# GL3520_4_Ports.net
KiCad netlist of a schematic drawn in Altium Designer
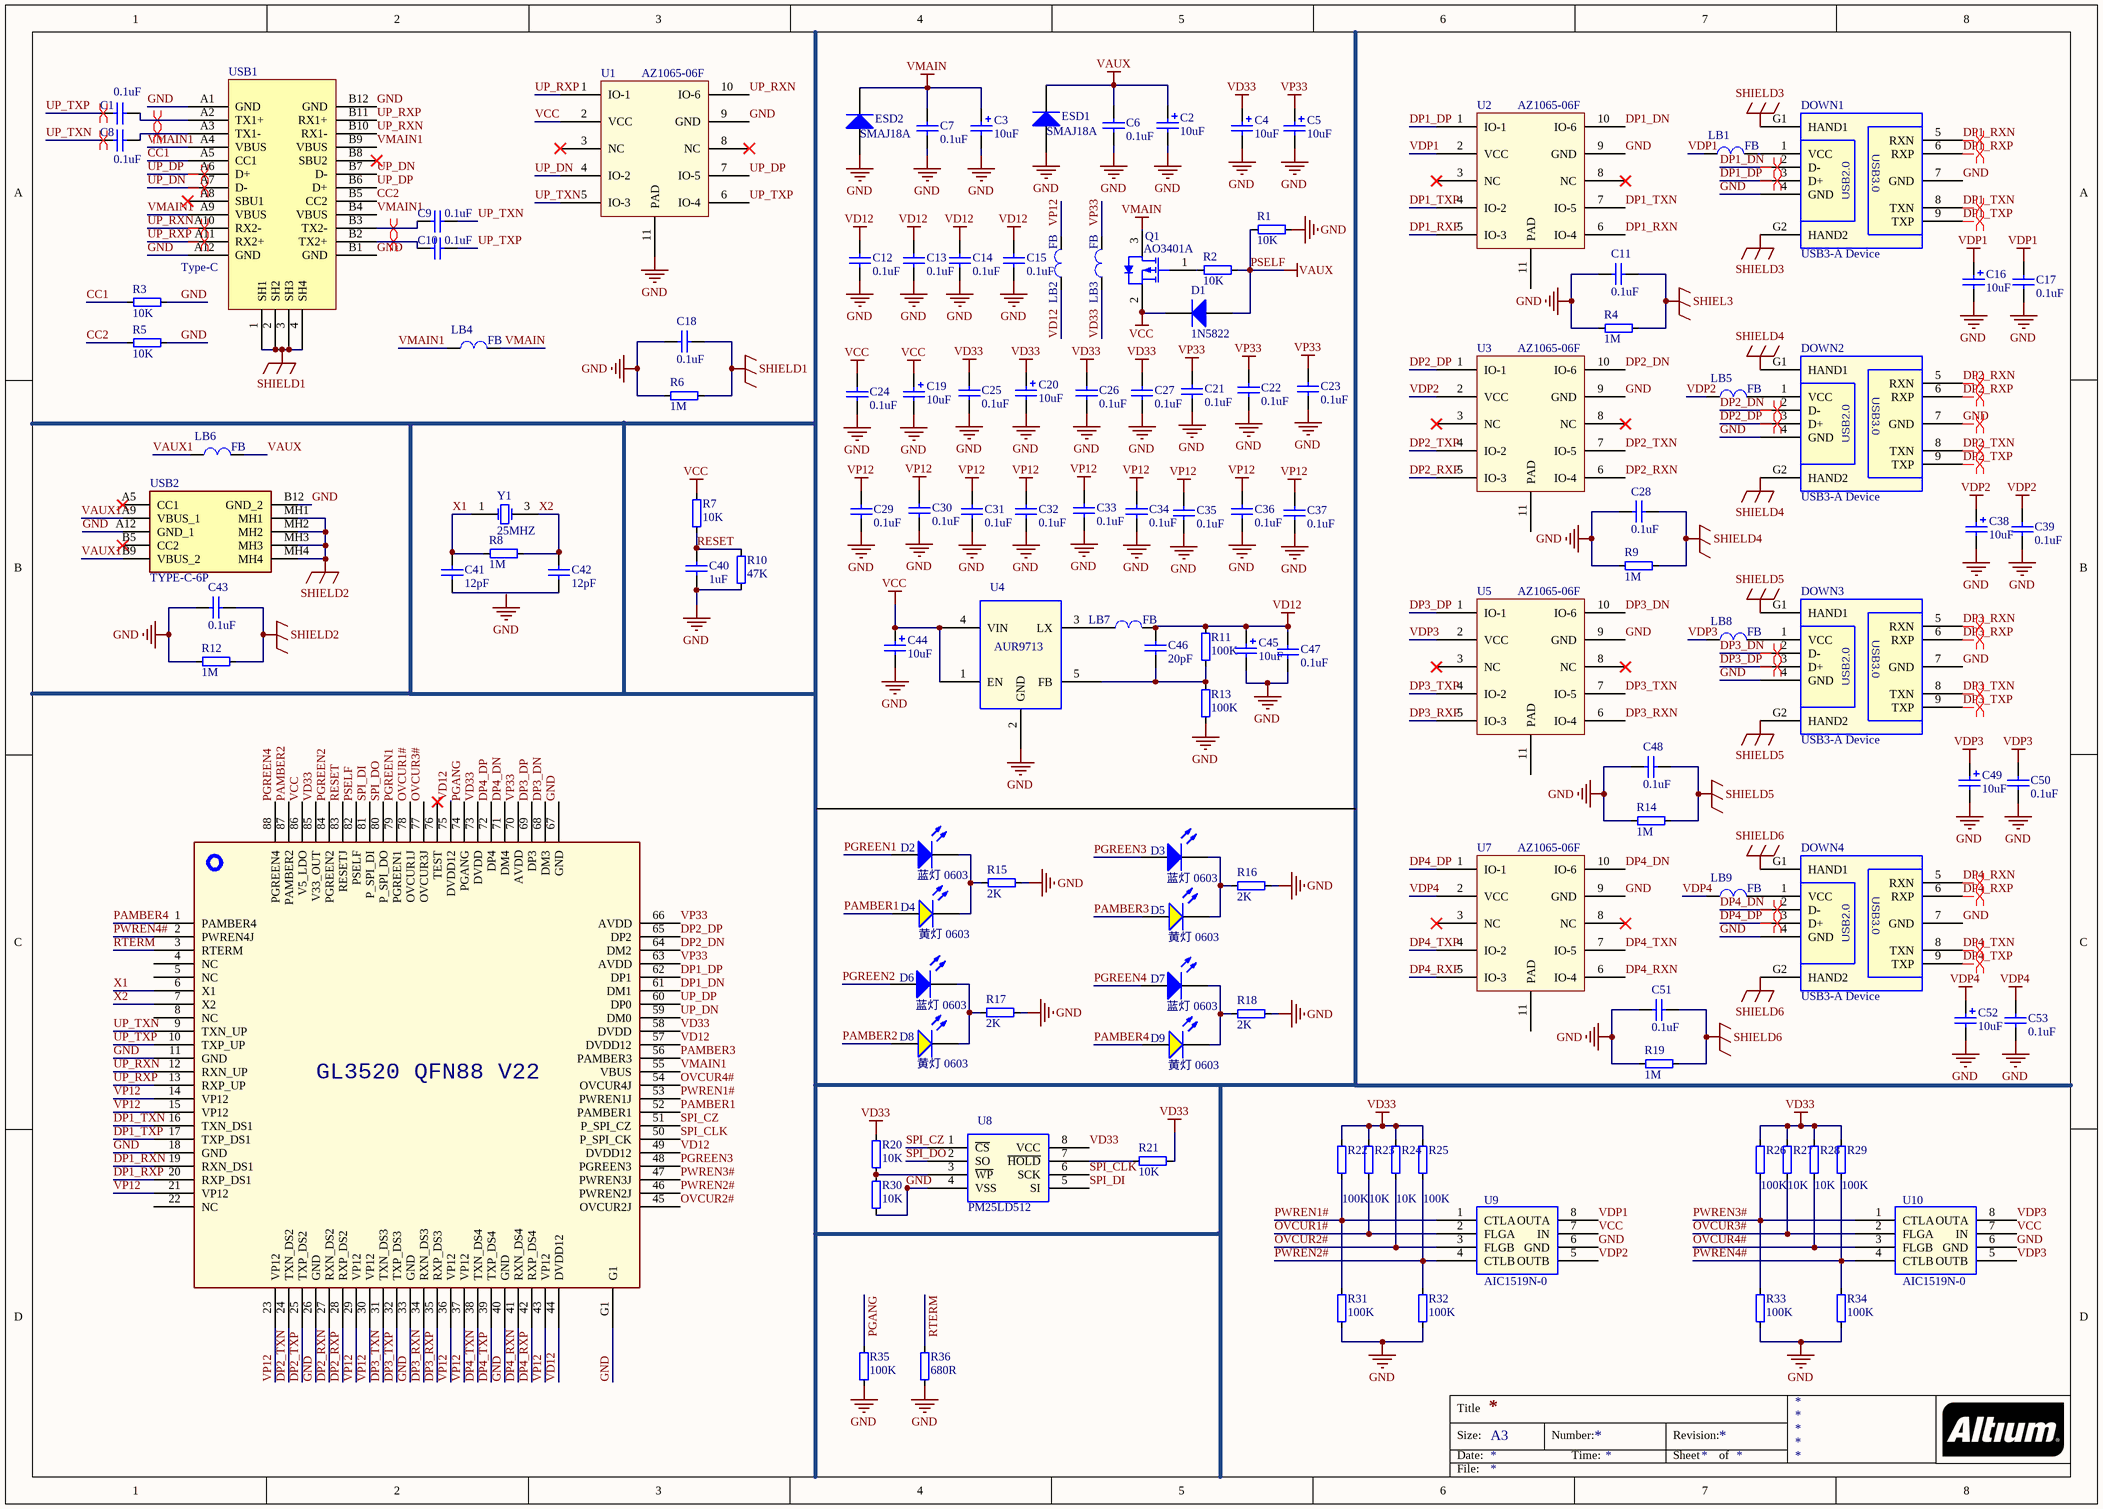
[diagram p0: GL3520 4 Ports.SchDoc]

(export (version "E")
  (design (tool "Eeschema 10.0.6"))
  (components
    (comp (ref "C1")
      (value "0.1uF")
      (footprint "0603_C")
      (description "贴片电容")
      (libsource (lib "嘉立创") (part "0603 2.2uF (225) 10% 16V"))
    )
    (comp (ref "C2")
      (value "10uF")
      (footprint "CASE-A_3216")
      (description "钽电容1206")
      (libsource (lib "嘉立创") (part "3216 10uF (106) 10% 16V"))
    )
    (comp (ref "C3")
      (value "10uF")
      (footprint "CASE-A_3216")
      (description "钽电容1206")
      (libsource (lib "嘉立创") (part "3216 10uF (106) 10% 16V"))
    )
    (comp (ref "C4")
      (value "10uF")
      (footprint "CASE-A_3216")
      (description "钽电容")
      (libsource (lib "嘉立创") (part "3216 10uF (106) 10% 16V"))
    )
    (comp (ref "C5")
      (value "10uF")
      (footprint "CASE-A_3216")
      (description "钽电容")
      (libsource (lib "嘉立创") (part "3216 10uF (106) 10% 16V"))
    )
    (comp (ref "C6")
      (value "0.1uF")
      (footprint "0603_C")
      (description "贴片电容")
      (libsource (lib "嘉立创") (part "0603 2.2uF (225) 10% 16V"))
    )
    (comp (ref "C7")
      (value "0.1uF")
      (footprint "0603_C")
      (description "贴片电容")
      (libsource (lib "嘉立创") (part "0603 2.2uF (225) 10% 16V"))
    )
    (comp (ref "C8")
      (value "0.1uF")
      (footprint "0603_C")
      (description "贴片电容")
      (libsource (lib "嘉立创") (part "0603 2.2uF (225) 10% 16V"))
    )
    (comp (ref "C9")
      (value "0.1uF")
      (footprint "0603_C")
      (description "贴片电容")
      (libsource (lib "嘉立创") (part "0603 2.2uF (225) 10% 16V"))
    )
    (comp (ref "C10")
      (value "0.1uF")
      (footprint "0603_C")
      (description "贴片电容")
      (libsource (lib "嘉立创") (part "0603 2.2uF (225) 10% 16V"))
    )
    (comp (ref "C11")
      (value "0.1uF")
      (footprint "0603_C")
      (description "贴片电容")
      (libsource (lib "嘉立创") (part "0603 2.2uF (225) 10% 16V"))
    )
    (comp (ref "C12")
      (value "0.1uF")
      (footprint "0603_C")
      (description "贴片电容")
      (libsource (lib "嘉立创") (part "0603 2.2uF (225) 10% 16V"))
    )
    (comp (ref "C13")
      (value "0.1uF")
      (footprint "0603_C")
      (description "贴片电容")
      (libsource (lib "嘉立创") (part "0603 2.2uF (225) 10% 16V"))
    )
    (comp (ref "C14")
      (value "0.1uF")
      (footprint "0603_C")
      (description "贴片电容")
      (libsource (lib "嘉立创") (part "0603 2.2uF (225) 10% 16V"))
    )
    (comp (ref "C15")
      (value "0.1uF")
      (footprint "0603_C")
      (description "贴片电容")
      (libsource (lib "嘉立创") (part "0603 2.2uF (225) 10% 16V"))
    )
    (comp (ref "C16")
      (value "10uF")
      (footprint "CASE-A_3216")
      (description "钽电容")
      (libsource (lib "嘉立创") (part "3216 10uF (106) 10% 16V"))
    )
    (comp (ref "C17")
      (value "0.1uF")
      (footprint "0603_C")
      (description "贴片电容")
      (libsource (lib "嘉立创") (part "0603 2.2uF (225) 10% 16V"))
    )
    (comp (ref "C18")
      (value "0.1uF")
      (footprint "0603_C")
      (description "贴片电容")
      (libsource (lib "嘉立创") (part "0603 2.2uF (225) 10% 16V"))
    )
    (comp (ref "C19")
      (value "10uF")
      (footprint "CASE-A_3216")
      (description "钽电容1206")
      (libsource (lib "嘉立创") (part "3216 10uF (106) 10% 16V"))
    )
    (comp (ref "C20")
      (value "10uF")
      (footprint "CASE-A_3216")
      (description "钽电容1206")
      (libsource (lib "嘉立创") (part "3216 10uF (106) 10% 16V"))
    )
    (comp (ref "C21")
      (value "0.1uF")
      (footprint "0603_C")
      (description "贴片电容")
      (libsource (lib "嘉立创") (part "0603 2.2uF (225) 10% 16V"))
    )
    (comp (ref "C22")
      (value "0.1uF")
      (footprint "0603_C")
      (description "贴片电容")
      (libsource (lib "嘉立创") (part "0603 2.2uF (225) 10% 16V"))
    )
    (comp (ref "C23")
      (value "0.1uF")
      (footprint "0603_C")
      (description "贴片电容")
      (libsource (lib "嘉立创") (part "0603 2.2uF (225) 10% 16V"))
    )
    (comp (ref "C24")
      (value "0.1uF")
      (footprint "0603_C")
      (description "贴片电容")
      (libsource (lib "嘉立创") (part "0603 2.2uF (225) 10% 16V"))
    )
    (comp (ref "C25")
      (value "0.1uF")
      (footprint "0603_C")
      (description "贴片电容")
      (libsource (lib "嘉立创") (part "0603 2.2uF (225) 10% 16V"))
    )
    (comp (ref "C26")
      (value "0.1uF")
      (footprint "0603_C")
      (description "贴片电容")
      (libsource (lib "嘉立创") (part "0603 2.2uF (225) 10% 16V"))
    )
    (comp (ref "C27")
      (value "0.1uF")
      (footprint "0603_C")
      (description "贴片电容")
      (libsource (lib "嘉立创") (part "0603 2.2uF (225) 10% 16V"))
    )
    (comp (ref "C28")
      (value "0.1uF")
      (footprint "0603_C")
      (description "贴片电容")
      (libsource (lib "嘉立创") (part "0603 2.2uF (225) 10% 16V"))
    )
    (comp (ref "C29")
      (value "0.1uF")
      (footprint "0603_C")
      (description "贴片电容")
      (libsource (lib "嘉立创") (part "0603 2.2uF (225) 10% 16V"))
    )
    (comp (ref "C30")
      (value "0.1uF")
      (footprint "0603_C")
      (description "贴片电容")
      (libsource (lib "嘉立创") (part "0603 2.2uF (225) 10% 16V"))
    )
    (comp (ref "C31")
      (value "0.1uF")
      (footprint "0603_C")
      (description "贴片电容")
      (libsource (lib "嘉立创") (part "0603 2.2uF (225) 10% 16V"))
    )
    (comp (ref "C32")
      (value "0.1uF")
      (footprint "0603_C")
      (description "贴片电容")
      (libsource (lib "嘉立创") (part "0603 2.2uF (225) 10% 16V"))
    )
    (comp (ref "C33")
      (value "0.1uF")
      (footprint "0603_C")
      (description "贴片电容")
      (libsource (lib "嘉立创") (part "0603 2.2uF (225) 10% 16V"))
    )
    (comp (ref "C34")
      (value "0.1uF")
      (footprint "0603_C")
      (description "贴片电容")
      (libsource (lib "嘉立创") (part "0603 2.2uF (225) 10% 16V"))
    )
    (comp (ref "C35")
      (value "0.1uF")
      (footprint "0603_C")
      (description "贴片电容")
      (libsource (lib "嘉立创") (part "0603 2.2uF (225) 10% 16V"))
    )
    (comp (ref "C36")
      (value "0.1uF")
      (footprint "0603_C")
      (description "贴片电容")
      (libsource (lib "嘉立创") (part "0603 2.2uF (225) 10% 16V"))
    )
    (comp (ref "C37")
      (value "0.1uF")
      (footprint "0603_C")
      (description "贴片电容")
      (libsource (lib "嘉立创") (part "0603 2.2uF (225) 10% 16V"))
    )
    (comp (ref "C38")
      (value "10uF")
      (footprint "CASE-A_3216")
      (description "钽电容")
      (libsource (lib "嘉立创") (part "3216 10uF (106) 10% 16V"))
    )
    (comp (ref "C39")
      (value "0.1uF")
      (footprint "0603_C")
      (description "贴片电容")
      (libsource (lib "嘉立创") (part "0603 2.2uF (225) 10% 16V"))
    )
    (comp (ref "C40")
      (value "1uF")
      (footprint "0603_C")
      (description "贴片电容")
      (libsource (lib "嘉立创") (part "0603 2.2uF (225) 10% 16V"))
    )
    (comp (ref "C41")
      (value "12pF")
      (footprint "0603_C")
      (description "贴片电容")
      (libsource (lib "嘉立创") (part "0603 2.2uF (225) 10% 16V"))
    )
    (comp (ref "C42")
      (value "12pF")
      (footprint "0603_C")
      (description "贴片电容")
      (libsource (lib "嘉立创") (part "0603 2.2uF (225) 10% 16V"))
    )
    (comp (ref "C43")
      (value "0.1uF")
      (footprint "0603_C")
      (description "贴片电容")
      (libsource (lib "嘉立创") (part "0603 2.2uF (225) 10% 16V"))
    )
    (comp (ref "C44")
      (value "10uF")
      (footprint "CASE-A_3216")
      (description "钽电容")
      (libsource (lib "嘉立创") (part "3216 10uF (106) 10% 16V"))
    )
    (comp (ref "C45")
      (value "10uF")
      (footprint "CASE-A_3216")
      (description "钽电容")
      (libsource (lib "嘉立创") (part "3216 10uF (106) 10% 16V"))
    )
    (comp (ref "C46")
      (value "20pF")
      (footprint "0603_C")
      (description "贴片电容")
      (libsource (lib "嘉立创") (part "0603 2.2uF (225) 10% 16V"))
    )
    (comp (ref "C47")
      (value "0.1uF")
      (footprint "0603_C")
      (description "贴片电容")
      (libsource (lib "嘉立创") (part "0603 2.2uF (225) 10% 16V"))
    )
    (comp (ref "C48")
      (value "0.1uF")
      (footprint "0603_C")
      (description "贴片电容")
      (libsource (lib "嘉立创") (part "0603 2.2uF (225) 10% 16V"))
    )
    (comp (ref "C49")
      (value "10uF")
      (footprint "CASE-A_3216")
      (description "钽电容")
      (libsource (lib "嘉立创") (part "3216 10uF (106) 10% 16V"))
    )
    (comp (ref "C50")
      (value "0.1uF")
      (footprint "0603_C")
      (description "贴片电容")
      (libsource (lib "嘉立创") (part "0603 2.2uF (225) 10% 16V"))
    )
    (comp (ref "C51")
      (value "0.1uF")
      (footprint "0603_C")
      (description "贴片电容")
      (libsource (lib "嘉立创") (part "0603 2.2uF (225) 10% 16V"))
    )
    (comp (ref "C52")
      (value "10uF")
      (footprint "CASE-A_3216")
      (description "钽电容")
      (libsource (lib "嘉立创") (part "3216 10uF (106) 10% 16V"))
    )
    (comp (ref "C53")
      (value "0.1uF")
      (footprint "0603_C")
      (description "贴片电容")
      (libsource (lib "嘉立创") (part "0603 2.2uF (225) 10% 16V"))
    )
    (comp (ref "D1")
      (value "1N5822")
      (footprint "DO-201AD")
      (description "3 Amp General Purpose Rectifier")
      (fields (field (name "PUBLISHER") "Altium Limited"))
      (libsource (lib "Miscellaneous Devices") (part "Diode 1N5400"))
    )
    (comp (ref "D2")
      (value "蓝灯 0603")
      (footprint "0603_LED_S1")
      (description "发光二极管")
      (libsource (lib "嘉立创") (part "0603 蓝灯"))
    )
    (comp (ref "D3")
      (value "蓝灯 0603")
      (footprint "0603_LED_S1")
      (description "发光二极管")
      (libsource (lib "嘉立创") (part "0603 蓝灯"))
    )
    (comp (ref "D4")
      (value "黄灯 0603")
      (footprint "0603_LED_S1")
      (description "发光二极管")
      (libsource (lib "嘉立创") (part "0603 黄灯"))
    )
    (comp (ref "D5")
      (value "黄灯 0603")
      (footprint "0603_LED_S1")
      (description "发光二极管")
      (libsource (lib "嘉立创") (part "0603 黄灯"))
    )
    (comp (ref "D6")
      (value "蓝灯 0603")
      (footprint "0603_LED_S1")
      (description "发光二极管")
      (libsource (lib "嘉立创") (part "0603 蓝灯"))
    )
    (comp (ref "D7")
      (value "蓝灯 0603")
      (footprint "0603_LED_S1")
      (description "发光二极管")
      (libsource (lib "嘉立创") (part "0603 蓝灯"))
    )
    (comp (ref "D8")
      (value "黄灯 0603")
      (footprint "0603_LED_S1")
      (description "发光二极管")
      (libsource (lib "嘉立创") (part "0603 黄灯"))
    )
    (comp (ref "D9")
      (value "黄灯 0603")
      (footprint "0603_LED_S1")
      (description "发光二极管")
      (libsource (lib "嘉立创") (part "0603 黄灯"))
    )
    (comp (ref "DOWN1")
      (value "USB3-A Device")
      (footprint "CND-USB3-A")
      (libsource (lib "*") (part "USB3-A_5"))
    )
    (comp (ref "DOWN2")
      (value "USB3-A Device")
      (footprint "CND-USB3-A")
      (libsource (lib "*") (part "USB3-A_5"))
    )
    (comp (ref "DOWN3")
      (value "USB3-A Device")
      (footprint "CND-USB3-A")
      (libsource (lib "*") (part "USB3-A_5"))
    )
    (comp (ref "DOWN4")
      (value "USB3-A Device")
      (footprint "CND-USB3-A")
      (libsource (lib "*") (part "USB3-A_5"))
    )
    (comp (ref "ESD1")
      (value "SMAJ18A")
      (footprint "VISH-DO-214AC-2_M")
      (fields
        (field (name "PARTNUMBER") "SMAJ12A-E3/5A")
        (field (name "MANUFACTURER") "Vishay Semiconductor")
      )
      (libsource (lib "Altium Content Vault") (part "VISH-K1A2-2"))
    )
    (comp (ref "ESD2")
      (value "SMAJ18A")
      (footprint "VISH-DO-214AC-2_M")
      (fields
        (field (name "PARTNUMBER") "SMAJ12A-E3/5A")
        (field (name "MANUFACTURER") "Vishay Semiconductor")
      )
      (libsource (lib "Altium Content Vault") (part "VISH-K1A2-2"))
    )
    (comp (ref "LB1") (value "FB") (footprint "LBS-0603") (libsource (lib "*") (part "L-0603")))
    (comp (ref "LB2") (value "FB") (footprint "LBS-0603") (libsource (lib "*") (part "L-0603")))
    (comp (ref "LB3") (value "FB") (footprint "LBS-0603") (libsource (lib "*") (part "L-0603")))
    (comp (ref "LB4") (value "FB") (footprint "LBS-0603") (libsource (lib "*") (part "L-0603")))
    (comp (ref "LB5") (value "FB") (footprint "LBS-0603") (libsource (lib "*") (part "L-0603")))
    (comp (ref "LB6") (value "FB") (footprint "LBS-0603") (libsource (lib "*") (part "L-0603")))
    (comp (ref "LB7") (value "FB") (footprint "LBS-0603") (libsource (lib "*") (part "L-0603")))
    (comp (ref "LB8") (value "FB") (footprint "LBS-0603") (libsource (lib "*") (part "L-0603")))
    (comp (ref "LB9") (value "FB") (footprint "LBS-0603") (libsource (lib "*") (part "L-0603")))
    (comp (ref "Q1")
      (value "AO3401A")
      (footprint "AO-SOT-23-3L_V")
      (description "P-Channel MOSFET, 30 V, 4 A, -55 to 150 degC, 3-Pin SOT-23-3L, RoHS, Tape and Reel")
      (fields (field (name "MANUFACTURER") "Alpha and Omega"))
      (libsource (lib "GL3520 4 Ports") (part "CMP-2000-05778-1"))
    )
    (comp (ref "R1") (value "10K") (footprint "R 0603_L") (libsource (lib "Jlink OB") (part "RES")))
    (comp (ref "R2") (value "10K") (footprint "R 0603_L") (libsource (lib "Jlink OB") (part "RES")))
    (comp (ref "R3") (value "10K") (footprint "R 0603_L") (libsource (lib "Jlink OB") (part "RES")))
    (comp (ref "R4") (value "1M") (footprint "R 0603_L") (libsource (lib "Jlink OB") (part "RES")))
    (comp (ref "R5") (value "10K") (footprint "R 0603_L") (libsource (lib "Jlink OB") (part "RES")))
    (comp (ref "R6") (value "1M") (footprint "R 0603_L") (libsource (lib "Jlink OB") (part "RES")))
    (comp (ref "R7") (value "10K") (footprint "R 0603_L") (libsource (lib "Jlink OB") (part "RES")))
    (comp (ref "R8") (value "1M") (footprint "R 0603_L") (libsource (lib "Jlink OB") (part "RES")))
    (comp (ref "R9") (value "1M") (footprint "R 0603_L") (libsource (lib "Jlink OB") (part "RES")))
    (comp (ref "R10") (value "47K") (footprint "R 0603_L") (libsource (lib "Jlink OB") (part "RES")))
    (comp (ref "R11") (value "100K") (footprint "R 0603_L") (libsource (lib "Jlink OB") (part "RES")))
    (comp (ref "R12") (value "1M") (footprint "R 0603_L") (libsource (lib "Jlink OB") (part "RES")))
    (comp (ref "R13") (value "100K") (footprint "R 0603_L") (libsource (lib "Jlink OB") (part "RES")))
    (comp (ref "R14") (value "1M") (footprint "R 0603_L") (libsource (lib "Jlink OB") (part "RES")))
    (comp (ref "R15") (value "2K") (footprint "R 0603_L") (libsource (lib "Jlink OB") (part "RES")))
    (comp (ref "R16") (value "2K") (footprint "R 0603_L") (libsource (lib "Jlink OB") (part "RES")))
    (comp (ref "R17") (value "2K") (footprint "R 0603_L") (libsource (lib "Jlink OB") (part "RES")))
    (comp (ref "R18") (value "2K") (footprint "R 0603_L") (libsource (lib "Jlink OB") (part "RES")))
    (comp (ref "R19") (value "1M") (footprint "R 0603_L") (libsource (lib "Jlink OB") (part "RES")))
    (comp (ref "R20") (value "10K") (footprint "R 0603_L") (libsource (lib "Jlink OB") (part "RES")))
    (comp (ref "R21") (value "10K") (footprint "R 0603_L") (libsource (lib "Jlink OB") (part "RES")))
    (comp (ref "R22") (value "100K") (footprint "R 0603_L") (libsource (lib "Jlink OB") (part "RES")))
    (comp (ref "R23") (value "10K") (footprint "R 0603_L") (libsource (lib "Jlink OB") (part "RES")))
    (comp (ref "R24") (value "10K") (footprint "R 0603_L") (libsource (lib "Jlink OB") (part "RES")))
    (comp (ref "R25") (value "100K") (footprint "R 0603_L") (libsource (lib "Jlink OB") (part "RES")))
    (comp (ref "R26") (value "100K") (footprint "R 0603_L") (libsource (lib "Jlink OB") (part "RES")))
    (comp (ref "R27") (value "10K") (footprint "R 0603_L") (libsource (lib "Jlink OB") (part "RES")))
    (comp (ref "R28") (value "10K") (footprint "R 0603_L") (libsource (lib "Jlink OB") (part "RES")))
    (comp (ref "R29") (value "100K") (footprint "R 0603_L") (libsource (lib "Jlink OB") (part "RES")))
    (comp (ref "R30") (value "10K") (footprint "R 0603_L") (libsource (lib "Jlink OB") (part "RES")))
    (comp (ref "R31") (value "100K") (footprint "R 0603_L") (libsource (lib "Jlink OB") (part "RES")))
    (comp (ref "R32") (value "100K") (footprint "R 0603_L") (libsource (lib "Jlink OB") (part "RES")))
    (comp (ref "R33") (value "100K") (footprint "R 0603_L") (libsource (lib "Jlink OB") (part "RES")))
    (comp (ref "R34") (value "100K") (footprint "R 0603_L") (libsource (lib "Jlink OB") (part "RES")))
    (comp (ref "R35") (value "100K") (footprint "R 0603_L") (libsource (lib "Jlink OB") (part "RES")))
    (comp (ref "R36") (value "680R") (footprint "R 0603_L") (libsource (lib "Jlink OB") (part "RES")))
    (comp (ref "U1")
      (value "AZ1065-06F")
      (description "晶炎AZ1065-06F.R7G DFN4120 丝印119 ESD/TVS静电保护二极管")
      (libsource (lib "GL3520 4 Ports") (part "AZ1065-06F"))
    )
    (comp (ref "U2")
      (value "AZ1065-06F")
      (description "晶炎AZ1065-06F.R7G DFN4120 丝印119 ESD/TVS静电保护二极管")
      (libsource (lib "GL3520 4 Ports") (part "AZ1065-06F"))
    )
    (comp (ref "U3")
      (value "AZ1065-06F")
      (description "晶炎AZ1065-06F.R7G DFN4120 丝印119 ESD/TVS静电保护二极管")
      (libsource (lib "GL3520 4 Ports") (part "AZ1065-06F"))
    )
    (comp (ref "U4")
      (value "AUR9713")
      (footprint "I-TSOT23-5P-2_9x1_6x0_95A")
      (libsource (lib "*") (part "AUR9705_3"))
    )
    (comp (ref "U5")
      (value "AZ1065-06F")
      (description "晶炎AZ1065-06F.R7G DFN4120 丝印119 ESD/TVS静电保护二极管")
      (libsource (lib "GL3520 4 Ports") (part "AZ1065-06F"))
    )
    (comp (ref "U6")
      (value "GL3520_QFN88_V094-1_22")
      (footprint "I-LQFP128-0_4A")
      (libsource (lib "GL3520 4 Ports") (part "GL3520_QFN88_V094-1_22"))
    )
    (comp (ref "U7")
      (value "AZ1065-06F")
      (description "晶炎AZ1065-06F.R7G DFN4120 丝印119 ESD/TVS静电保护二极管")
      (libsource (lib "GL3520 4 Ports") (part "AZ1065-06F"))
    )
    (comp (ref "U8")
      (value "PM25LD512")
      (footprint "I-SOP8-1_27A")
      (libsource (lib "*") (part "CAT25C128/256"))
    )
    (comp (ref "U9")
      (value "AIC1519N-0")
      (footprint "I-SOP8-1_27A")
      (libsource (lib "*") (part "AIC1526-SOP"))
    )
    (comp (ref "U10")
      (value "AIC1519N-0")
      (footprint "I-SOP8-1_27A")
      (libsource (lib "*") (part "AIC1526-SOP"))
    )
    (comp (ref "USB1")
      (value "Type-C")
      (footprint "PCBComponent_1")
      (libsource (lib "Jlink OB") (part "Type-C"))
    )
    (comp (ref "USB2")
      (value "TYPE-C-6P")
      (footprint "SamacSys:TYPEC 6P")
      (description "Connector")
      (fields (field (name "MANUFACTURER_PART_NUMBER") "TYPE-C-31-M-17"))
      (libsource (lib "SamacSys") (part "TYPE-C-31-M-17"))
    )
    (comp (ref "Y1")
      (value "25MHZ")
      (footprint "SMD-3225_4P")
      (description "贴片晶振")
      (libsource (lib "嘉立创") (part "SMD-3225_4P  25MHZ 12PF 10PPM"))
    )
  )
  (nets
    (net (code "1") (name "/CC1") (class "Default")
      (node (ref "R3") (pin "1") (pinfunction "1_1") (pintype "passive"))
      (node (ref "USB1") (pin "A5") (pinfunction "CC1_A5") (pintype "passive"))
    )
    (net (code "2") (name "/CC2") (class "Default")
      (node (ref "R5") (pin "1") (pinfunction "1_1") (pintype "passive"))
      (node (ref "USB1") (pin "B5") (pinfunction "CC2_B5") (pintype "passive"))
    )
    (net (code "3") (name "/DP1_DN") (class "Default")
      (node (ref "DOWN1") (pin "2") (pinfunction "D-_2") (pintype "passive"))
      (node (ref "U2") (pin "10") (pinfunction "IO-6_10") (pintype "passive"))
      (node (ref "U6") (pin "61") (pinfunction "DM1_61") (pintype "passive"))
    )
    (net (code "4") (name "/DP1_DP") (class "Default")
      (node (ref "DOWN1") (pin "3") (pinfunction "D+_3") (pintype "passive"))
      (node (ref "U2") (pin "1") (pinfunction "IO-1_1") (pintype "passive"))
      (node (ref "U6") (pin "62") (pinfunction "DP1_62") (pintype "passive"))
    )
    (net (code "5") (name "/DP1_RXN") (class "Default")
      (node (ref "DOWN1") (pin "5") (pinfunction "RXN_5") (pintype "passive"))
      (node (ref "U2") (pin "6") (pinfunction "IO-4_6") (pintype "passive"))
      (node (ref "U6") (pin "19") (pinfunction "RXN_DS1_19") (pintype "passive"))
    )
    (net (code "6") (name "/DP1_RXP") (class "Default")
      (node (ref "DOWN1") (pin "6") (pinfunction "RXP_6") (pintype "passive"))
      (node (ref "U2") (pin "5") (pinfunction "IO-3_5") (pintype "passive"))
      (node (ref "U6") (pin "20") (pinfunction "RXP_DS1_20") (pintype "passive"))
    )
    (net (code "7") (name "/DP1_TXN") (class "Default")
      (node (ref "DOWN1") (pin "8") (pinfunction "TXN_8") (pintype "passive"))
      (node (ref "U2") (pin "7") (pinfunction "IO-5_7") (pintype "passive"))
      (node (ref "U6") (pin "16") (pinfunction "TXN_DS1_16") (pintype "passive"))
    )
    (net (code "8") (name "/DP1_TXP") (class "Default")
      (node (ref "DOWN1") (pin "9") (pinfunction "TXP_9") (pintype "passive"))
      (node (ref "U2") (pin "4") (pinfunction "IO-2_4") (pintype "passive"))
      (node (ref "U6") (pin "17") (pinfunction "TXP_DS1_17") (pintype "passive"))
    )
    (net (code "9") (name "/DP2_DN") (class "Default")
      (node (ref "DOWN2") (pin "2") (pinfunction "D-_2") (pintype "passive"))
      (node (ref "U3") (pin "10") (pinfunction "IO-6_10") (pintype "passive"))
      (node (ref "U6") (pin "64") (pinfunction "DM2_64") (pintype "passive"))
    )
    (net (code "10") (name "/DP2_DP") (class "Default")
      (node (ref "DOWN2") (pin "3") (pinfunction "D+_3") (pintype "passive"))
      (node (ref "U3") (pin "1") (pinfunction "IO-1_1") (pintype "passive"))
      (node (ref "U6") (pin "65") (pinfunction "DP2_65") (pintype "passive"))
    )
    (net (code "11") (name "/DP2_RXN") (class "Default")
      (node (ref "DOWN2") (pin "5") (pinfunction "RXN_5") (pintype "passive"))
      (node (ref "U3") (pin "6") (pinfunction "IO-4_6") (pintype "passive"))
      (node (ref "U6") (pin "27") (pinfunction "RXN_DS2_27") (pintype "passive"))
    )
    (net (code "12") (name "/DP2_RXP") (class "Default")
      (node (ref "DOWN2") (pin "6") (pinfunction "RXP_6") (pintype "passive"))
      (node (ref "U3") (pin "5") (pinfunction "IO-3_5") (pintype "passive"))
      (node (ref "U6") (pin "28") (pinfunction "RXP_DS2_28") (pintype "passive"))
    )
    (net (code "13") (name "/DP2_TXN") (class "Default")
      (node (ref "DOWN2") (pin "8") (pinfunction "TXN_8") (pintype "passive"))
      (node (ref "U3") (pin "7") (pinfunction "IO-5_7") (pintype "passive"))
      (node (ref "U6") (pin "24") (pinfunction "TXN_DS2_24") (pintype "passive"))
    )
    (net (code "14") (name "/DP2_TXP") (class "Default")
      (node (ref "DOWN2") (pin "9") (pinfunction "TXP_9") (pintype "passive"))
      (node (ref "U3") (pin "4") (pinfunction "IO-2_4") (pintype "passive"))
      (node (ref "U6") (pin "25") (pinfunction "TXP_DS2_25") (pintype "passive"))
    )
    (net (code "15") (name "/DP3_DN") (class "Default")
      (node (ref "DOWN3") (pin "2") (pinfunction "D-_2") (pintype "passive"))
      (node (ref "U5") (pin "10") (pinfunction "IO-6_10") (pintype "passive"))
      (node (ref "U6") (pin "68") (pinfunction "DM3_68") (pintype "passive"))
    )
    (net (code "16") (name "/DP3_DP") (class "Default")
      (node (ref "DOWN3") (pin "3") (pinfunction "D+_3") (pintype "passive"))
      (node (ref "U5") (pin "1") (pinfunction "IO-1_1") (pintype "passive"))
      (node (ref "U6") (pin "69") (pinfunction "DP3_69") (pintype "passive"))
    )
    (net (code "17") (name "/DP3_RXN") (class "Default")
      (node (ref "DOWN3") (pin "5") (pinfunction "RXN_5") (pintype "passive"))
      (node (ref "U5") (pin "6") (pinfunction "IO-4_6") (pintype "passive"))
      (node (ref "U6") (pin "34") (pinfunction "RXN_DS3_34") (pintype "passive"))
    )
    (net (code "18") (name "/DP3_RXP") (class "Default")
      (node (ref "DOWN3") (pin "6") (pinfunction "RXP_6") (pintype "passive"))
      (node (ref "U5") (pin "5") (pinfunction "IO-3_5") (pintype "passive"))
      (node (ref "U6") (pin "35") (pinfunction "RXP_DS3_35") (pintype "passive"))
    )
    (net (code "19") (name "/DP3_TXN") (class "Default")
      (node (ref "DOWN3") (pin "8") (pinfunction "TXN_8") (pintype "passive"))
      (node (ref "U5") (pin "7") (pinfunction "IO-5_7") (pintype "passive"))
      (node (ref "U6") (pin "31") (pinfunction "TXN_DS3_31") (pintype "passive"))
    )
    (net (code "20") (name "/DP3_TXP") (class "Default")
      (node (ref "DOWN3") (pin "9") (pinfunction "TXP_9") (pintype "passive"))
      (node (ref "U5") (pin "4") (pinfunction "IO-2_4") (pintype "passive"))
      (node (ref "U6") (pin "32") (pinfunction "TXP_DS3_32") (pintype "passive"))
    )
    (net (code "21") (name "/DP4_DN") (class "Default")
      (node (ref "DOWN4") (pin "2") (pinfunction "D-_2") (pintype "passive"))
      (node (ref "U6") (pin "71") (pinfunction "DM4_71") (pintype "passive"))
      (node (ref "U7") (pin "10") (pinfunction "IO-6_10") (pintype "passive"))
    )
    (net (code "22") (name "/DP4_DP") (class "Default")
      (node (ref "DOWN4") (pin "3") (pinfunction "D+_3") (pintype "passive"))
      (node (ref "U6") (pin "72") (pinfunction "DP4_72") (pintype "passive"))
      (node (ref "U7") (pin "1") (pinfunction "IO-1_1") (pintype "passive"))
    )
    (net (code "23") (name "/DP4_RXN") (class "Default")
      (node (ref "DOWN4") (pin "5") (pinfunction "RXN_5") (pintype "passive"))
      (node (ref "U6") (pin "41") (pinfunction "RXN_DS4_41") (pintype "passive"))
      (node (ref "U7") (pin "6") (pinfunction "IO-4_6") (pintype "passive"))
    )
    (net (code "24") (name "/DP4_RXP") (class "Default")
      (node (ref "DOWN4") (pin "6") (pinfunction "RXP_6") (pintype "passive"))
      (node (ref "U6") (pin "42") (pinfunction "RXP_DS4_42") (pintype "passive"))
      (node (ref "U7") (pin "5") (pinfunction "IO-3_5") (pintype "passive"))
    )
    (net (code "25") (name "/DP4_TXN") (class "Default")
      (node (ref "DOWN4") (pin "8") (pinfunction "TXN_8") (pintype "passive"))
      (node (ref "U6") (pin "38") (pinfunction "TXN_DS4_38") (pintype "passive"))
      (node (ref "U7") (pin "7") (pinfunction "IO-5_7") (pintype "passive"))
    )
    (net (code "26") (name "/DP4_TXP") (class "Default")
      (node (ref "DOWN4") (pin "9") (pinfunction "TXP_9") (pintype "passive"))
      (node (ref "U6") (pin "39") (pinfunction "TXP_DS4_39") (pintype "passive"))
      (node (ref "U7") (pin "4") (pinfunction "IO-2_4") (pintype "passive"))
    )
    (net (code "27") (name "/OVCUR1#") (class "Default")
      (node (ref "R23") (pin "2") (pinfunction "2_2") (pintype "passive"))
      (node (ref "U6") (pin "78") (pinfunction "OVCUR1J_78") (pintype "passive"))
      (node (ref "U9") (pin "2") (pinfunction "FLGA_2") (pintype "passive"))
    )
    (net (code "28") (name "/OVCUR2#") (class "Default")
      (node (ref "R24") (pin "2") (pinfunction "2_2") (pintype "passive"))
      (node (ref "U6") (pin "45") (pinfunction "OVCUR2J_45") (pintype "passive"))
      (node (ref "U9") (pin "3") (pinfunction "FLGB_3") (pintype "passive"))
    )
    (net (code "29") (name "/OVCUR3#") (class "Default")
      (node (ref "R27") (pin "2") (pinfunction "2_2") (pintype "passive"))
      (node (ref "U10") (pin "2") (pinfunction "FLGA_2") (pintype "passive"))
      (node (ref "U6") (pin "77") (pinfunction "OVCUR3J_77") (pintype "passive"))
    )
    (net (code "30") (name "/OVCUR4#") (class "Default")
      (node (ref "R28") (pin "2") (pinfunction "2_2") (pintype "passive"))
      (node (ref "U10") (pin "3") (pinfunction "FLGB_3") (pintype "passive"))
      (node (ref "U6") (pin "54") (pinfunction "OVCUR4J_54") (pintype "passive"))
    )
    (net (code "31") (name "/PAMBER1") (class "Default")
      (node (ref "D4") (pin "A") (pinfunction "A_A") (pintype "passive"))
      (node (ref "U6") (pin "52") (pinfunction "PAMBER1_52") (pintype "passive"))
    )
    (net (code "32") (name "/PAMBER2") (class "Default")
      (node (ref "D8") (pin "A") (pinfunction "A_A") (pintype "passive"))
      (node (ref "U6") (pin "87") (pinfunction "PAMBER2_87") (pintype "passive"))
    )
    (net (code "33") (name "/PAMBER3") (class "Default")
      (node (ref "D5") (pin "A") (pinfunction "A_A") (pintype "passive"))
      (node (ref "U6") (pin "56") (pinfunction "PAMBER3_56") (pintype "passive"))
    )
    (net (code "34") (name "/PAMBER4") (class "Default")
      (node (ref "D9") (pin "A") (pinfunction "A_A") (pintype "passive"))
      (node (ref "U6") (pin "1") (pinfunction "PAMBER4_1") (pintype "passive"))
    )
    (net (code "35") (name "/PGANG") (class "Default")
      (node (ref "R35") (pin "1") (pinfunction "1_1") (pintype "passive"))
      (node (ref "U6") (pin "74") (pinfunction "PGANG_74") (pintype "passive"))
    )
    (net (code "36") (name "/PGREEN1") (class "Default")
      (node (ref "D2") (pin "A") (pinfunction "A_A") (pintype "passive"))
      (node (ref "U6") (pin "79") (pinfunction "PGREEN1_79") (pintype "passive"))
    )
    (net (code "37") (name "/PGREEN2") (class "Default")
      (node (ref "D6") (pin "A") (pinfunction "A_A") (pintype "passive"))
      (node (ref "U6") (pin "84") (pinfunction "PGREEN2_84") (pintype "passive"))
    )
    (net (code "38") (name "/PGREEN3") (class "Default")
      (node (ref "D3") (pin "A") (pinfunction "A_A") (pintype "passive"))
      (node (ref "U6") (pin "48") (pinfunction "PGREEN3_48") (pintype "passive"))
    )
    (net (code "39") (name "/PGREEN4") (class "Default")
      (node (ref "D7") (pin "A") (pinfunction "A_A") (pintype "passive"))
      (node (ref "U6") (pin "88") (pinfunction "PGREEN4_88") (pintype "passive"))
    )
    (net (code "40") (name "/PWREN1#") (class "Default")
      (node (ref "R22") (pin "2") (pinfunction "2_2") (pintype "passive"))
      (node (ref "R31") (pin "1") (pinfunction "1_1") (pintype "passive"))
      (node (ref "U6") (pin "53") (pinfunction "PWREN1J_53") (pintype "passive"))
      (node (ref "U9") (pin "1") (pinfunction "CTLA_1") (pintype "passive"))
    )
    (net (code "41") (name "/PWREN2#") (class "Default")
      (node (ref "R25") (pin "2") (pinfunction "2_2") (pintype "passive"))
      (node (ref "R32") (pin "1") (pinfunction "1_1") (pintype "passive"))
      (node (ref "U6") (pin "46") (pinfunction "PWREN2J_46") (pintype "passive"))
      (node (ref "U9") (pin "4") (pinfunction "CTLB_4") (pintype "passive"))
    )
    (net (code "42") (name "/PWREN3#") (class "Default")
      (node (ref "R26") (pin "2") (pinfunction "2_2") (pintype "passive"))
      (node (ref "R33") (pin "1") (pinfunction "1_1") (pintype "passive"))
      (node (ref "U10") (pin "1") (pinfunction "CTLA_1") (pintype "passive"))
      (node (ref "U6") (pin "47") (pinfunction "PWREN3J_47") (pintype "passive"))
    )
    (net (code "43") (name "/PWREN4#") (class "Default")
      (node (ref "R29") (pin "2") (pinfunction "2_2") (pintype "passive"))
      (node (ref "R34") (pin "1") (pinfunction "1_1") (pintype "passive"))
      (node (ref "U10") (pin "4") (pinfunction "CTLB_4") (pintype "passive"))
      (node (ref "U6") (pin "2") (pinfunction "PWREN4J_2") (pintype "passive"))
    )
    (net (code "44") (name "/RESET") (class "Default")
      (node (ref "C40") (pin "2") (pinfunction "2_2") (pintype "passive"))
      (node (ref "R10") (pin "2") (pinfunction "2_2") (pintype "passive"))
      (node (ref "R7") (pin "1") (pinfunction "1_1") (pintype "passive"))
      (node (ref "U6") (pin "83") (pinfunction "RESETJ_83") (pintype "passive"))
    )
    (net (code "45") (name "/RTERM") (class "Default")
      (node (ref "R36") (pin "1") (pinfunction "1_1") (pintype "passive"))
      (node (ref "U6") (pin "3") (pinfunction "RTERM_3") (pintype "passive"))
    )
    (net (code "46") (name "/SPI_CLK") (class "Default")
      (node (ref "U6") (pin "50") (pinfunction "P_SPI_CK_50") (pintype "passive"))
      (node (ref "U8") (pin "6") (pinfunction "SCK_6") (pintype "passive"))
    )
    (net (code "47") (name "/SPI_CZ") (class "Default")
      (node (ref "U6") (pin "51") (pinfunction "P_SPI_CZ_51") (pintype "passive"))
      (node (ref "U8") (pin "1") (pinfunction "~{CS}_1") (pintype "passive"))
    )
    (net (code "48") (name "/SPI_DI") (class "Default")
      (node (ref "U6") (pin "81") (pinfunction "P_SPI_DI_81") (pintype "passive"))
      (node (ref "U8") (pin "5") (pinfunction "SI_5") (pintype "passive"))
    )
    (net (code "49") (name "/SPI_DO") (class "Default")
      (node (ref "U6") (pin "80") (pinfunction "P_SPI_DO_80") (pintype "passive"))
      (node (ref "U8") (pin "2") (pinfunction "SO_2") (pintype "passive"))
    )
    (net (code "50") (name "/UP_DN") (class "Default")
      (node (ref "U1") (pin "4") (pinfunction "IO-2_4") (pintype "passive"))
      (node (ref "U6") (pin "59") (pinfunction "DM0_59") (pintype "passive"))
      (node (ref "USB1") (pin "A7") (pinfunction "D-_A7") (pintype "passive"))
      (node (ref "USB1") (pin "B7") (pinfunction "D-_B7") (pintype "passive"))
    )
    (net (code "51") (name "/UP_DP") (class "Default")
      (node (ref "U1") (pin "7") (pinfunction "IO-5_7") (pintype "passive"))
      (node (ref "U6") (pin "60") (pinfunction "DP0_60") (pintype "passive"))
      (node (ref "USB1") (pin "A6") (pinfunction "D+_A6") (pintype "passive"))
      (node (ref "USB1") (pin "B6") (pinfunction "D+_B6") (pintype "passive"))
    )
    (net (code "52") (name "/UP_RXN") (class "Default")
      (node (ref "U1") (pin "10") (pinfunction "IO-6_10") (pintype "passive"))
      (node (ref "U6") (pin "12") (pinfunction "RXN_UP_12") (pintype "passive"))
      (node (ref "USB1") (pin "A10") (pinfunction "RX2-_A10") (pintype "passive"))
      (node (ref "USB1") (pin "B10") (pinfunction "RX1-_B10") (pintype "passive"))
    )
    (net (code "53") (name "/UP_RXP") (class "Default")
      (node (ref "U1") (pin "1") (pinfunction "IO-1_1") (pintype "passive"))
      (node (ref "U6") (pin "13") (pinfunction "RXP_UP_13") (pintype "passive"))
      (node (ref "USB1") (pin "A11") (pinfunction "RX2+_A11") (pintype "passive"))
      (node (ref "USB1") (pin "B11") (pinfunction "RX1+_B11") (pintype "passive"))
    )
    (net (code "54") (name "/UP_TXN") (class "Default")
      (node (ref "C8") (pin "2") (pinfunction "2_2") (pintype "passive"))
      (node (ref "C9") (pin "1") (pinfunction "1_1") (pintype "passive"))
      (node (ref "U1") (pin "5") (pinfunction "IO-3_5") (pintype "passive"))
      (node (ref "U6") (pin "9") (pinfunction "TXN_UP_9") (pintype "passive"))
    )
    (net (code "55") (name "/UP_TXP") (class "Default")
      (node (ref "C1") (pin "2") (pinfunction "2_2") (pintype "passive"))
      (node (ref "C10") (pin "1") (pinfunction "1_1") (pintype "passive"))
      (node (ref "U1") (pin "6") (pinfunction "IO-4_6") (pintype "passive"))
      (node (ref "U6") (pin "10") (pinfunction "TXP_UP_10") (pintype "passive"))
    )
    (net (code "56") (name "/VAUX1") (class "Default")
      (node (ref "LB6") (pin "1") (pinfunction "1_1") (pintype "passive"))
      (node (ref "USB2") (pin "A9") (pinfunction "VBUS_1_A9") (pintype "passive"))
      (node (ref "USB2") (pin "B9") (pinfunction "VBUS_2_B9") (pintype "passive"))
    )
    (net (code "57") (name "/VMAIN1") (class "Default")
      (node (ref "LB4") (pin "1") (pinfunction "1_1") (pintype "passive"))
      (node (ref "U6") (pin "55") (pinfunction "VBUS_55") (pintype "passive"))
      (node (ref "USB1") (pin "A4") (pinfunction "VBUS_A4") (pintype "passive"))
      (node (ref "USB1") (pin "A9") (pinfunction "VBUS_A9") (pintype "passive"))
      (node (ref "USB1") (pin "B4") (pinfunction "VBUS_B4") (pintype "passive"))
      (node (ref "USB1") (pin "B9") (pinfunction "VBUS_B9") (pintype "passive"))
    )
    (net (code "58") (name "/X1") (class "Default")
      (node (ref "C41") (pin "2") (pinfunction "2_2") (pintype "passive"))
      (node (ref "R8") (pin "1") (pinfunction "1_1") (pintype "passive"))
      (node (ref "U6") (pin "6") (pinfunction "X1_6") (pintype "passive"))
      (node (ref "Y1") (pin "1") (pinfunction "OSC1_1") (pintype "passive"))
    )
    (net (code "59") (name "/X2") (class "Default")
      (node (ref "C42") (pin "2") (pinfunction "2_2") (pintype "passive"))
      (node (ref "R8") (pin "2") (pinfunction "2_2") (pintype "passive"))
      (node (ref "U6") (pin "7") (pinfunction "X2_7") (pintype "passive"))
      (node (ref "Y1") (pin "3") (pinfunction "OSC2_3") (pintype "passive"))
    )
    (net (code "60") (name "GND") (class "Default")
      (node (ref "C11") (pin "1") (pinfunction "1_1") (pintype "passive"))
      (node (ref "C12") (pin "1") (pinfunction "1_1") (pintype "passive"))
      (node (ref "C13") (pin "1") (pinfunction "1_1") (pintype "passive"))
      (node (ref "C14") (pin "1") (pinfunction "1_1") (pintype "passive"))
      (node (ref "C15") (pin "1") (pinfunction "1_1") (pintype "passive"))
      (node (ref "C16") (pin "2") (pinfunction "2_2") (pintype "passive"))
      (node (ref "C17") (pin "1") (pinfunction "1_1") (pintype "passive"))
      (node (ref "C18") (pin "1") (pinfunction "1_1") (pintype "passive"))
      (node (ref "C19") (pin "2") (pinfunction "2_2") (pintype "passive"))
      (node (ref "C2") (pin "2") (pinfunction "2_2") (pintype "passive"))
      (node (ref "C20") (pin "2") (pinfunction "2_2") (pintype "passive"))
      (node (ref "C21") (pin "1") (pinfunction "1_1") (pintype "passive"))
      (node (ref "C22") (pin "1") (pinfunction "1_1") (pintype "passive"))
      (node (ref "C23") (pin "1") (pinfunction "1_1") (pintype "passive"))
      (node (ref "C24") (pin "1") (pinfunction "1_1") (pintype "passive"))
      (node (ref "C25") (pin "1") (pinfunction "1_1") (pintype "passive"))
      (node (ref "C26") (pin "1") (pinfunction "1_1") (pintype "passive"))
      (node (ref "C27") (pin "1") (pinfunction "1_1") (pintype "passive"))
      (node (ref "C28") (pin "1") (pinfunction "1_1") (pintype "passive"))
      (node (ref "C29") (pin "1") (pinfunction "1_1") (pintype "passive"))
      (node (ref "C3") (pin "2") (pinfunction "2_2") (pintype "passive"))
      (node (ref "C30") (pin "1") (pinfunction "1_1") (pintype "passive"))
      (node (ref "C31") (pin "1") (pinfunction "1_1") (pintype "passive"))
      (node (ref "C32") (pin "1") (pinfunction "1_1") (pintype "passive"))
      (node (ref "C33") (pin "1") (pinfunction "1_1") (pintype "passive"))
      (node (ref "C34") (pin "1") (pinfunction "1_1") (pintype "passive"))
      (node (ref "C35") (pin "1") (pinfunction "1_1") (pintype "passive"))
      (node (ref "C36") (pin "1") (pinfunction "1_1") (pintype "passive"))
      (node (ref "C37") (pin "1") (pinfunction "1_1") (pintype "passive"))
      (node (ref "C38") (pin "2") (pinfunction "2_2") (pintype "passive"))
      (node (ref "C39") (pin "1") (pinfunction "1_1") (pintype "passive"))
      (node (ref "C4") (pin "2") (pinfunction "2_2") (pintype "passive"))
      (node (ref "C40") (pin "1") (pinfunction "1_1") (pintype "passive"))
      (node (ref "C43") (pin "1") (pinfunction "1_1") (pintype "passive"))
      (node (ref "C44") (pin "2") (pinfunction "2_2") (pintype "passive"))
      (node (ref "C45") (pin "2") (pinfunction "2_2") (pintype "passive"))
      (node (ref "C47") (pin "1") (pinfunction "1_1") (pintype "passive"))
      (node (ref "C48") (pin "1") (pinfunction "1_1") (pintype "passive"))
      (node (ref "C49") (pin "2") (pinfunction "2_2") (pintype "passive"))
      (node (ref "C5") (pin "2") (pinfunction "2_2") (pintype "passive"))
      (node (ref "C50") (pin "1") (pinfunction "1_1") (pintype "passive"))
      (node (ref "C51") (pin "1") (pinfunction "1_1") (pintype "passive"))
      (node (ref "C52") (pin "2") (pinfunction "2_2") (pintype "passive"))
      (node (ref "C53") (pin "1") (pinfunction "1_1") (pintype "passive"))
      (node (ref "C6") (pin "1") (pinfunction "1_1") (pintype "passive"))
      (node (ref "C7") (pin "1") (pinfunction "1_1") (pintype "passive"))
      (node (ref "DOWN1") (pin "4") (pinfunction "GND_4") (pintype "power_in"))
      (node (ref "DOWN1") (pin "7") (pinfunction "GND_7") (pintype "power_in"))
      (node (ref "DOWN2") (pin "4") (pinfunction "GND_4") (pintype "power_in"))
      (node (ref "DOWN2") (pin "7") (pinfunction "GND_7") (pintype "power_in"))
      (node (ref "DOWN3") (pin "4") (pinfunction "GND_4") (pintype "power_in"))
      (node (ref "DOWN3") (pin "7") (pinfunction "GND_7") (pintype "power_in"))
      (node (ref "DOWN4") (pin "4") (pinfunction "GND_4") (pintype "power_in"))
      (node (ref "DOWN4") (pin "7") (pinfunction "GND_7") (pintype "power_in"))
      (node (ref "ESD1") (pin "2") (pinfunction "A_2") (pintype "passive"))
      (node (ref "ESD2") (pin "2") (pinfunction "A_2") (pintype "passive"))
      (node (ref "R1") (pin "2") (pinfunction "2_2") (pintype "passive"))
      (node (ref "R10") (pin "1") (pinfunction "1_1") (pintype "passive"))
      (node (ref "R12") (pin "2") (pinfunction "2_2") (pintype "passive"))
      (node (ref "R13") (pin "2") (pinfunction "2_2") (pintype "passive"))
      (node (ref "R14") (pin "2") (pinfunction "2_2") (pintype "passive"))
      (node (ref "R15") (pin "1") (pinfunction "1_1") (pintype "passive"))
      (node (ref "R16") (pin "1") (pinfunction "1_1") (pintype "passive"))
      (node (ref "R17") (pin "1") (pinfunction "1_1") (pintype "passive"))
      (node (ref "R18") (pin "1") (pinfunction "1_1") (pintype "passive"))
      (node (ref "R19") (pin "2") (pinfunction "2_2") (pintype "passive"))
      (node (ref "R3") (pin "2") (pinfunction "2_2") (pintype "passive"))
      (node (ref "R30") (pin "2") (pinfunction "2_2") (pintype "passive"))
      (node (ref "R31") (pin "2") (pinfunction "2_2") (pintype "passive"))
      (node (ref "R32") (pin "2") (pinfunction "2_2") (pintype "passive"))
      (node (ref "R33") (pin "2") (pinfunction "2_2") (pintype "passive"))
      (node (ref "R34") (pin "2") (pinfunction "2_2") (pintype "passive"))
      (node (ref "R35") (pin "2") (pinfunction "2_2") (pintype "passive"))
      (node (ref "R36") (pin "2") (pinfunction "2_2") (pintype "passive"))
      (node (ref "R4") (pin "2") (pinfunction "2_2") (pintype "passive"))
      (node (ref "R5") (pin "2") (pinfunction "2_2") (pintype "passive"))
      (node (ref "R6") (pin "2") (pinfunction "2_2") (pintype "passive"))
      (node (ref "R9") (pin "2") (pinfunction "2_2") (pintype "passive"))
      (node (ref "U1") (pin "11") (pinfunction "PAD_11") (pintype "passive"))
      (node (ref "U1") (pin "9") (pinfunction "GND_9") (pintype "passive"))
      (node (ref "U10") (pin "6") (pinfunction "GND_6") (pintype "passive"))
      (node (ref "U2") (pin "9") (pinfunction "GND_9") (pintype "passive"))
      (node (ref "U3") (pin "9") (pinfunction "GND_9") (pintype "passive"))
      (node (ref "U4") (pin "2") (pinfunction "GND_2") (pintype "passive"))
      (node (ref "U5") (pin "9") (pinfunction "GND_9") (pintype "passive"))
      (node (ref "U6") (pin "11") (pinfunction "GND_11") (pintype "passive"))
      (node (ref "U6") (pin "18") (pinfunction "GND_18") (pintype "passive"))
      (node (ref "U6") (pin "26") (pinfunction "GND_26") (pintype "passive"))
      (node (ref "U6") (pin "33") (pinfunction "GND_33") (pintype "passive"))
      (node (ref "U6") (pin "40") (pinfunction "GND_40") (pintype "passive"))
      (node (ref "U6") (pin "67") (pinfunction "GND_67") (pintype "passive"))
      (node (ref "U6") (pin "G1") (pinfunction "G1_G1") (pintype "passive"))
      (node (ref "U7") (pin "9") (pinfunction "GND_9") (pintype "passive"))
      (node (ref "U8") (pin "4") (pinfunction "VSS_4") (pintype "passive"))
      (node (ref "U9") (pin "6") (pinfunction "GND_6") (pintype "passive"))
      (node (ref "USB1") (pin "A1") (pinfunction "GND_A1") (pintype "passive"))
      (node (ref "USB1") (pin "A12") (pinfunction "GND_A12") (pintype "passive"))
      (node (ref "USB1") (pin "B1") (pinfunction "GND_B1") (pintype "passive"))
      (node (ref "USB1") (pin "B12") (pinfunction "GND_B12") (pintype "passive"))
      (node (ref "USB2") (pin "A12") (pinfunction "GND_1_A12") (pintype "passive"))
      (node (ref "USB2") (pin "B12") (pinfunction "GND_2_B12") (pintype "passive"))
    )
    (net (code "61") (name "Net-(C41-Pad1)") (class "Default")
      (node (ref "C41") (pin "1") (pinfunction "1_1") (pintype "passive"))
      (node (ref "C42") (pin "1") (pinfunction "1_1") (pintype "passive"))
    )
    (net (code "62") (name "Net-(D2-PadK)") (class "Default")
      (node (ref "D2") (pin "K") (pinfunction "K_K") (pintype "passive"))
      (node (ref "D4") (pin "K") (pinfunction "K_K") (pintype "passive"))
      (node (ref "R15") (pin "2") (pinfunction "2_2") (pintype "passive"))
    )
    (net (code "63") (name "Net-(D3-PadK)") (class "Default")
      (node (ref "D3") (pin "K") (pinfunction "K_K") (pintype "passive"))
      (node (ref "D5") (pin "K") (pinfunction "K_K") (pintype "passive"))
      (node (ref "R16") (pin "2") (pinfunction "2_2") (pintype "passive"))
    )
    (net (code "64") (name "Net-(D6-PadK)") (class "Default")
      (node (ref "D6") (pin "K") (pinfunction "K_K") (pintype "passive"))
      (node (ref "D8") (pin "K") (pinfunction "K_K") (pintype "passive"))
      (node (ref "R17") (pin "2") (pinfunction "2_2") (pintype "passive"))
    )
    (net (code "65") (name "Net-(D7-PadK)") (class "Default")
      (node (ref "D7") (pin "K") (pinfunction "K_K") (pintype "passive"))
      (node (ref "D9") (pin "K") (pinfunction "K_K") (pintype "passive"))
      (node (ref "R18") (pin "2") (pinfunction "2_2") (pintype "passive"))
    )
    (net (code "66") (name "Net-(DOWN1-VCC)") (class "Default")
      (node (ref "DOWN1") (pin "1") (pinfunction "VCC_1") (pintype "power_in"))
      (node (ref "LB1") (pin "2") (pinfunction "2_2") (pintype "passive"))
    )
    (net (code "67") (name "Net-(DOWN2-VCC)") (class "Default")
      (node (ref "DOWN2") (pin "1") (pinfunction "VCC_1") (pintype "power_in"))
      (node (ref "LB5") (pin "2") (pinfunction "2_2") (pintype "passive"))
    )
    (net (code "68") (name "Net-(DOWN3-VCC)") (class "Default")
      (node (ref "DOWN3") (pin "1") (pinfunction "VCC_1") (pintype "power_in"))
      (node (ref "LB8") (pin "2") (pinfunction "2_2") (pintype "passive"))
    )
    (net (code "69") (name "Net-(DOWN4-VCC)") (class "Default")
      (node (ref "DOWN4") (pin "1") (pinfunction "VCC_1") (pintype "power_in"))
      (node (ref "LB9") (pin "2") (pinfunction "2_2") (pintype "passive"))
    )
    (net (code "70") (name "Net-(Q1-GATE)") (class "Default")
      (node (ref "Q1") (pin "1") (pinfunction "GATE_1") (pintype "passive"))
      (node (ref "R2") (pin "1") (pinfunction "1_1") (pintype "passive"))
    )
    (net (code "71") (name "Net-(U4-FB)") (class "Default")
      (node (ref "C46") (pin "1") (pinfunction "1_1") (pintype "passive"))
      (node (ref "R11") (pin "2") (pinfunction "2_2") (pintype "passive"))
      (node (ref "R13") (pin "1") (pinfunction "1_1") (pintype "passive"))
      (node (ref "U4") (pin "5") (pinfunction "FB_5") (pintype "passive"))
    )
    (net (code "72") (name "Net-(U4-LX)") (class "Default")
      (node (ref "LB7") (pin "1") (pinfunction "1_1") (pintype "passive"))
      (node (ref "U4") (pin "3") (pinfunction "LX_3") (pintype "passive"))
    )
    (net (code "73") (name "Net-(U8-~{HOLD})") (class "Default")
      (node (ref "R21") (pin "1") (pinfunction "1_1") (pintype "passive"))
      (node (ref "U8") (pin "7") (pinfunction "~{HOLD}_7") (pintype "passive"))
    )
    (net (code "74") (name "Net-(U8-~{WP})") (class "Default")
      (node (ref "R20") (pin "2") (pinfunction "2_2") (pintype "passive"))
      (node (ref "R30") (pin "1") (pinfunction "1_1") (pintype "passive"))
      (node (ref "U8") (pin "3") (pinfunction "~{WP}_3") (pintype "passive"))
    )
    (net (code "75") (name "Net-(USB1-TX1+)") (class "Default")
      (node (ref "C1") (pin "1") (pinfunction "1_1") (pintype "passive"))
      (node (ref "USB1") (pin "A2") (pinfunction "TX1+_A2") (pintype "passive"))
    )
    (net (code "76") (name "Net-(USB1-TX1-)") (class "Default")
      (node (ref "C8") (pin "1") (pinfunction "1_1") (pintype "passive"))
      (node (ref "USB1") (pin "A3") (pinfunction "TX1-_A3") (pintype "passive"))
    )
    (net (code "77") (name "Net-(USB1-TX2+)") (class "Default")
      (node (ref "C10") (pin "2") (pinfunction "2_2") (pintype "passive"))
      (node (ref "USB1") (pin "B2") (pinfunction "TX2+_B2") (pintype "passive"))
    )
    (net (code "78") (name "Net-(USB1-TX2-)") (class "Default")
      (node (ref "C9") (pin "2") (pinfunction "2_2") (pintype "passive"))
      (node (ref "USB1") (pin "B3") (pinfunction "TX2-_B3") (pintype "passive"))
    )
    (net (code "79") (name "SHIEL3") (class "Default")
      (node (ref "C11") (pin "2") (pinfunction "2_2") (pintype "passive"))
      (node (ref "R4") (pin "1") (pinfunction "1_1") (pintype "passive"))
    )
    (net (code "80") (name "SHIELD1") (class "Default")
      (node (ref "C18") (pin "2") (pinfunction "2_2") (pintype "passive"))
      (node (ref "R6") (pin "1") (pinfunction "1_1") (pintype "passive"))
      (node (ref "USB1") (pin "1") (pinfunction "SH1_1") (pintype "passive"))
      (node (ref "USB1") (pin "2") (pinfunction "SH2_2") (pintype "passive"))
      (node (ref "USB1") (pin "3") (pinfunction "SH3_3") (pintype "passive"))
      (node (ref "USB1") (pin "4") (pinfunction "SH4_4") (pintype "passive"))
    )
    (net (code "81") (name "SHIELD2") (class "Default")
      (node (ref "C43") (pin "2") (pinfunction "2_2") (pintype "passive"))
      (node (ref "R12") (pin "1") (pinfunction "1_1") (pintype "passive"))
      (node (ref "USB2") (pin "MH1") (pinfunction "MH1_MH1") (pintype "passive"))
      (node (ref "USB2") (pin "MH2") (pinfunction "MH2_MH2") (pintype "passive"))
      (node (ref "USB2") (pin "MH3") (pinfunction "MH3_MH3") (pintype "passive"))
      (node (ref "USB2") (pin "MH4") (pinfunction "MH4_MH4") (pintype "passive"))
    )
    (net (code "82") (name "SHIELD3") (class "Default")
      (node (ref "DOWN1") (pin "G1") (pinfunction "HAND1_G1") (pintype "passive"))
      (node (ref "DOWN1") (pin "G2") (pinfunction "HAND2_G2") (pintype "passive"))
    )
    (net (code "83") (name "SHIELD4") (class "Default")
      (node (ref "C28") (pin "2") (pinfunction "2_2") (pintype "passive"))
      (node (ref "DOWN2") (pin "G1") (pinfunction "HAND1_G1") (pintype "passive"))
      (node (ref "DOWN2") (pin "G2") (pinfunction "HAND2_G2") (pintype "passive"))
      (node (ref "R9") (pin "1") (pinfunction "1_1") (pintype "passive"))
    )
    (net (code "84") (name "SHIELD5") (class "Default")
      (node (ref "C48") (pin "2") (pinfunction "2_2") (pintype "passive"))
      (node (ref "DOWN3") (pin "G1") (pinfunction "HAND1_G1") (pintype "passive"))
      (node (ref "DOWN3") (pin "G2") (pinfunction "HAND2_G2") (pintype "passive"))
      (node (ref "R14") (pin "1") (pinfunction "1_1") (pintype "passive"))
    )
    (net (code "85") (name "SHIELD6") (class "Default")
      (node (ref "C51") (pin "2") (pinfunction "2_2") (pintype "passive"))
      (node (ref "DOWN4") (pin "G1") (pinfunction "HAND1_G1") (pintype "passive"))
      (node (ref "DOWN4") (pin "G2") (pinfunction "HAND2_G2") (pintype "passive"))
      (node (ref "R19") (pin "1") (pinfunction "1_1") (pintype "passive"))
    )
    (net (code "86") (name "VAUX") (class "Default")
      (node (ref "C2") (pin "1") (pinfunction "1_1") (pintype "passive"))
      (node (ref "C6") (pin "2") (pinfunction "2_2") (pintype "passive"))
      (node (ref "D1") (pin "1") (pinfunction "A_1") (pintype "passive"))
      (node (ref "ESD1") (pin "1") (pinfunction "K_1") (pintype "passive"))
      (node (ref "LB6") (pin "2") (pinfunction "2_2") (pintype "passive"))
      (node (ref "R1") (pin "1") (pinfunction "1_1") (pintype "passive"))
      (node (ref "R2") (pin "2") (pinfunction "2_2") (pintype "passive"))
      (node (ref "U6") (pin "82") (pinfunction "PSELF_82") (pintype "passive"))
    )
    (net (code "87") (name "VCC") (class "Default")
      (node (ref "C19") (pin "1") (pinfunction "1_1") (pintype "passive"))
      (node (ref "C24") (pin "2") (pinfunction "2_2") (pintype "passive"))
      (node (ref "C44") (pin "1") (pinfunction "1_1") (pintype "passive"))
      (node (ref "D1") (pin "2") (pinfunction "K_2") (pintype "passive"))
      (node (ref "Q1") (pin "2") (pinfunction "SOURCE_2") (pintype "passive"))
      (node (ref "R7") (pin "2") (pinfunction "2_2") (pintype "passive"))
      (node (ref "U1") (pin "2") (pinfunction "VCC_2") (pintype "passive"))
      (node (ref "U10") (pin "7") (pinfunction "IN_7") (pintype "passive"))
      (node (ref "U4") (pin "1") (pinfunction "EN_1") (pintype "passive"))
      (node (ref "U4") (pin "4") (pinfunction "VIN_4") (pintype "passive"))
      (node (ref "U6") (pin "86") (pinfunction "V5_LDO_86") (pintype "passive"))
      (node (ref "U9") (pin "7") (pinfunction "IN_7") (pintype "passive"))
    )
    (net (code "88") (name "VD12") (class "Default")
      (node (ref "C12") (pin "2") (pinfunction "2_2") (pintype "passive"))
      (node (ref "C13") (pin "2") (pinfunction "2_2") (pintype "passive"))
      (node (ref "C14") (pin "2") (pinfunction "2_2") (pintype "passive"))
      (node (ref "C15") (pin "2") (pinfunction "2_2") (pintype "passive"))
      (node (ref "C45") (pin "1") (pinfunction "1_1") (pintype "passive"))
      (node (ref "C46") (pin "2") (pinfunction "2_2") (pintype "passive"))
      (node (ref "C47") (pin "2") (pinfunction "2_2") (pintype "passive"))
      (node (ref "LB2") (pin "1") (pinfunction "1_1") (pintype "passive"))
      (node (ref "LB7") (pin "2") (pinfunction "2_2") (pintype "passive"))
      (node (ref "R11") (pin "1") (pinfunction "1_1") (pintype "passive"))
      (node (ref "U6") (pin "44") (pinfunction "DVDD12_44") (pintype "passive"))
      (node (ref "U6") (pin "49") (pinfunction "DVDD12_49") (pintype "passive"))
      (node (ref "U6") (pin "57") (pinfunction "DVDD12_57") (pintype "passive"))
      (node (ref "U6") (pin "75") (pinfunction "DVDD12_75") (pintype "passive"))
    )
    (net (code "89") (name "VD33") (class "Default")
      (node (ref "C20") (pin "1") (pinfunction "1_1") (pintype "passive"))
      (node (ref "C25") (pin "2") (pinfunction "2_2") (pintype "passive"))
      (node (ref "C26") (pin "2") (pinfunction "2_2") (pintype "passive"))
      (node (ref "C27") (pin "2") (pinfunction "2_2") (pintype "passive"))
      (node (ref "C4") (pin "1") (pinfunction "1_1") (pintype "passive"))
      (node (ref "LB3") (pin "1") (pinfunction "1_1") (pintype "passive"))
      (node (ref "R20") (pin "1") (pinfunction "1_1") (pintype "passive"))
      (node (ref "R21") (pin "2") (pinfunction "2_2") (pintype "passive"))
      (node (ref "R22") (pin "1") (pinfunction "1_1") (pintype "passive"))
      (node (ref "R23") (pin "1") (pinfunction "1_1") (pintype "passive"))
      (node (ref "R24") (pin "1") (pinfunction "1_1") (pintype "passive"))
      (node (ref "R25") (pin "1") (pinfunction "1_1") (pintype "passive"))
      (node (ref "R26") (pin "1") (pinfunction "1_1") (pintype "passive"))
      (node (ref "R27") (pin "1") (pinfunction "1_1") (pintype "passive"))
      (node (ref "R28") (pin "1") (pinfunction "1_1") (pintype "passive"))
      (node (ref "R29") (pin "1") (pinfunction "1_1") (pintype "passive"))
      (node (ref "U6") (pin "58") (pinfunction "DVDD_58") (pintype "passive"))
      (node (ref "U6") (pin "73") (pinfunction "DVDD_73") (pintype "passive"))
      (node (ref "U6") (pin "85") (pinfunction "V33_OUT_85") (pintype "passive"))
      (node (ref "U8") (pin "8") (pinfunction "VCC_8") (pintype "passive"))
    )
    (net (code "90") (name "VDP1") (class "Default")
      (node (ref "C16") (pin "1") (pinfunction "1_1") (pintype "passive"))
      (node (ref "C17") (pin "2") (pinfunction "2_2") (pintype "passive"))
      (node (ref "LB1") (pin "1") (pinfunction "1_1") (pintype "passive"))
      (node (ref "U2") (pin "2") (pinfunction "VCC_2") (pintype "passive"))
      (node (ref "U9") (pin "8") (pinfunction "OUTA_8") (pintype "passive"))
    )
    (net (code "91") (name "VDP2") (class "Default")
      (node (ref "C38") (pin "1") (pinfunction "1_1") (pintype "passive"))
      (node (ref "C39") (pin "2") (pinfunction "2_2") (pintype "passive"))
      (node (ref "LB5") (pin "1") (pinfunction "1_1") (pintype "passive"))
      (node (ref "U3") (pin "2") (pinfunction "VCC_2") (pintype "passive"))
      (node (ref "U9") (pin "5") (pinfunction "OUTB_5") (pintype "passive"))
    )
    (net (code "92") (name "VDP3") (class "Default")
      (node (ref "C49") (pin "1") (pinfunction "1_1") (pintype "passive"))
      (node (ref "C50") (pin "2") (pinfunction "2_2") (pintype "passive"))
      (node (ref "LB8") (pin "1") (pinfunction "1_1") (pintype "passive"))
      (node (ref "U10") (pin "5") (pinfunction "OUTB_5") (pintype "passive"))
      (node (ref "U10") (pin "8") (pinfunction "OUTA_8") (pintype "passive"))
      (node (ref "U5") (pin "2") (pinfunction "VCC_2") (pintype "passive"))
    )
    (net (code "93") (name "VDP4") (class "Default")
      (node (ref "C52") (pin "1") (pinfunction "1_1") (pintype "passive"))
      (node (ref "C53") (pin "2") (pinfunction "2_2") (pintype "passive"))
      (node (ref "LB9") (pin "1") (pinfunction "1_1") (pintype "passive"))
      (node (ref "U7") (pin "2") (pinfunction "VCC_2") (pintype "passive"))
    )
    (net (code "94") (name "VMAIN") (class "Default")
      (node (ref "C3") (pin "1") (pinfunction "1_1") (pintype "passive"))
      (node (ref "C7") (pin "2") (pinfunction "2_2") (pintype "passive"))
      (node (ref "ESD2") (pin "1") (pinfunction "K_1") (pintype "passive"))
      (node (ref "LB4") (pin "2") (pinfunction "2_2") (pintype "passive"))
      (node (ref "Q1") (pin "3") (pinfunction "DRAIN_3") (pintype "passive"))
    )
    (net (code "95") (name "VP12") (class "Default")
      (node (ref "C29") (pin "2") (pinfunction "2_2") (pintype "passive"))
      (node (ref "C30") (pin "2") (pinfunction "2_2") (pintype "passive"))
      (node (ref "C31") (pin "2") (pinfunction "2_2") (pintype "passive"))
      (node (ref "C32") (pin "2") (pinfunction "2_2") (pintype "passive"))
      (node (ref "C33") (pin "2") (pinfunction "2_2") (pintype "passive"))
      (node (ref "C34") (pin "2") (pinfunction "2_2") (pintype "passive"))
      (node (ref "C35") (pin "2") (pinfunction "2_2") (pintype "passive"))
      (node (ref "C36") (pin "2") (pinfunction "2_2") (pintype "passive"))
      (node (ref "C37") (pin "2") (pinfunction "2_2") (pintype "passive"))
      (node (ref "LB2") (pin "2") (pinfunction "2_2") (pintype "passive"))
      (node (ref "U6") (pin "14") (pinfunction "VP12_14") (pintype "passive"))
      (node (ref "U6") (pin "15") (pinfunction "VP12_15") (pintype "passive"))
      (node (ref "U6") (pin "21") (pinfunction "VP12_21") (pintype "passive"))
      (node (ref "U6") (pin "23") (pinfunction "VP12_23") (pintype "passive"))
      (node (ref "U6") (pin "29") (pinfunction "VP12_29") (pintype "passive"))
      (node (ref "U6") (pin "30") (pinfunction "VP12_30") (pintype "passive"))
      (node (ref "U6") (pin "36") (pinfunction "VP12_36") (pintype "passive"))
      (node (ref "U6") (pin "37") (pinfunction "VP12_37") (pintype "passive"))
      (node (ref "U6") (pin "43") (pinfunction "VP12_43") (pintype "passive"))
    )
    (net (code "96") (name "VP33") (class "Default")
      (node (ref "C21") (pin "2") (pinfunction "2_2") (pintype "passive"))
      (node (ref "C22") (pin "2") (pinfunction "2_2") (pintype "passive"))
      (node (ref "C23") (pin "2") (pinfunction "2_2") (pintype "passive"))
      (node (ref "C5") (pin "1") (pinfunction "1_1") (pintype "passive"))
      (node (ref "LB3") (pin "2") (pinfunction "2_2") (pintype "passive"))
      (node (ref "U6") (pin "63") (pinfunction "AVDD_63") (pintype "passive"))
      (node (ref "U6") (pin "66") (pinfunction "AVDD_66") (pintype "passive"))
      (node (ref "U6") (pin "70") (pinfunction "AVDD_70") (pintype "passive"))
    )
    (net (code "97") (name "unconnected-(U1-NC-Pad3)") (class "Default")
      (node (ref "U1") (pin "3") (pinfunction "NC_3") (pintype "passive+no_connect"))
    )
    (net (code "98") (name "unconnected-(U1-NC-Pad8)") (class "Default")
      (node (ref "U1") (pin "8") (pinfunction "NC_8") (pintype "passive+no_connect"))
    )
    (net (code "99") (name "unconnected-(U2-NC-Pad3)") (class "Default")
      (node (ref "U2") (pin "3") (pinfunction "NC_3") (pintype "passive+no_connect"))
    )
    (net (code "100") (name "unconnected-(U2-NC-Pad8)") (class "Default")
      (node (ref "U2") (pin "8") (pinfunction "NC_8") (pintype "passive+no_connect"))
    )
    (net (code "101") (name "unconnected-(U2-PAD-Pad11)") (class "Default")
      (node (ref "U2") (pin "11") (pinfunction "PAD_11") (pintype "passive"))
    )
    (net (code "102") (name "unconnected-(U3-NC-Pad3)") (class "Default")
      (node (ref "U3") (pin "3") (pinfunction "NC_3") (pintype "passive+no_connect"))
    )
    (net (code "103") (name "unconnected-(U3-NC-Pad8)") (class "Default")
      (node (ref "U3") (pin "8") (pinfunction "NC_8") (pintype "passive+no_connect"))
    )
    (net (code "104") (name "unconnected-(U3-PAD-Pad11)") (class "Default")
      (node (ref "U3") (pin "11") (pinfunction "PAD_11") (pintype "passive"))
    )
    (net (code "105") (name "unconnected-(U5-NC-Pad3)") (class "Default")
      (node (ref "U5") (pin "3") (pinfunction "NC_3") (pintype "passive+no_connect"))
    )
    (net (code "106") (name "unconnected-(U5-NC-Pad8)") (class "Default")
      (node (ref "U5") (pin "8") (pinfunction "NC_8") (pintype "passive+no_connect"))
    )
    (net (code "107") (name "unconnected-(U5-PAD-Pad11)") (class "Default")
      (node (ref "U5") (pin "11") (pinfunction "PAD_11") (pintype "passive"))
    )
    (net (code "108") (name "unconnected-(U6-NC-Pad4)") (class "Default")
      (node (ref "U6") (pin "4") (pinfunction "NC_4") (pintype "passive"))
    )
    (net (code "109") (name "unconnected-(U6-NC-Pad5)") (class "Default")
      (node (ref "U6") (pin "5") (pinfunction "NC_5") (pintype "passive"))
    )
    (net (code "110") (name "unconnected-(U6-NC-Pad8)") (class "Default")
      (node (ref "U6") (pin "8") (pinfunction "NC_8") (pintype "passive"))
    )
    (net (code "111") (name "unconnected-(U6-NC-Pad22)") (class "Default")
      (node (ref "U6") (pin "22") (pinfunction "NC_22") (pintype "passive"))
    )
    (net (code "112") (name "unconnected-(U6-TEST-Pad76)") (class "Default")
      (node (ref "U6") (pin "76") (pinfunction "TEST_76") (pintype "passive+no_connect"))
    )
    (net (code "113") (name "unconnected-(U7-NC-Pad3)") (class "Default")
      (node (ref "U7") (pin "3") (pinfunction "NC_3") (pintype "passive+no_connect"))
    )
    (net (code "114") (name "unconnected-(U7-NC-Pad8)") (class "Default")
      (node (ref "U7") (pin "8") (pinfunction "NC_8") (pintype "passive+no_connect"))
    )
    (net (code "115") (name "unconnected-(U7-PAD-Pad11)") (class "Default")
      (node (ref "U7") (pin "11") (pinfunction "PAD_11") (pintype "passive"))
    )
    (net (code "116") (name "unconnected-(USB1-SBU1-PadA8)") (class "Default")
      (node (ref "USB1") (pin "A8") (pinfunction "SBU1_A8") (pintype "passive+no_connect"))
    )
    (net (code "117") (name "unconnected-(USB1-SBU2-PadB8)") (class "Default")
      (node (ref "USB1") (pin "B8") (pinfunction "SBU2_B8") (pintype "passive+no_connect"))
    )
    (net (code "118") (name "unconnected-(USB2-CC1-PadA5)") (class "Default")
      (node (ref "USB2") (pin "A5") (pinfunction "CC1_A5") (pintype "passive+no_connect"))
    )
    (net (code "119") (name "unconnected-(USB2-CC2-PadB5)") (class "Default")
      (node (ref "USB2") (pin "B5") (pinfunction "CC2_B5") (pintype "passive+no_connect"))
    )
  )
)
